# Sheet2.net
KiCad netlist of a schematic drawn in Altium Designer
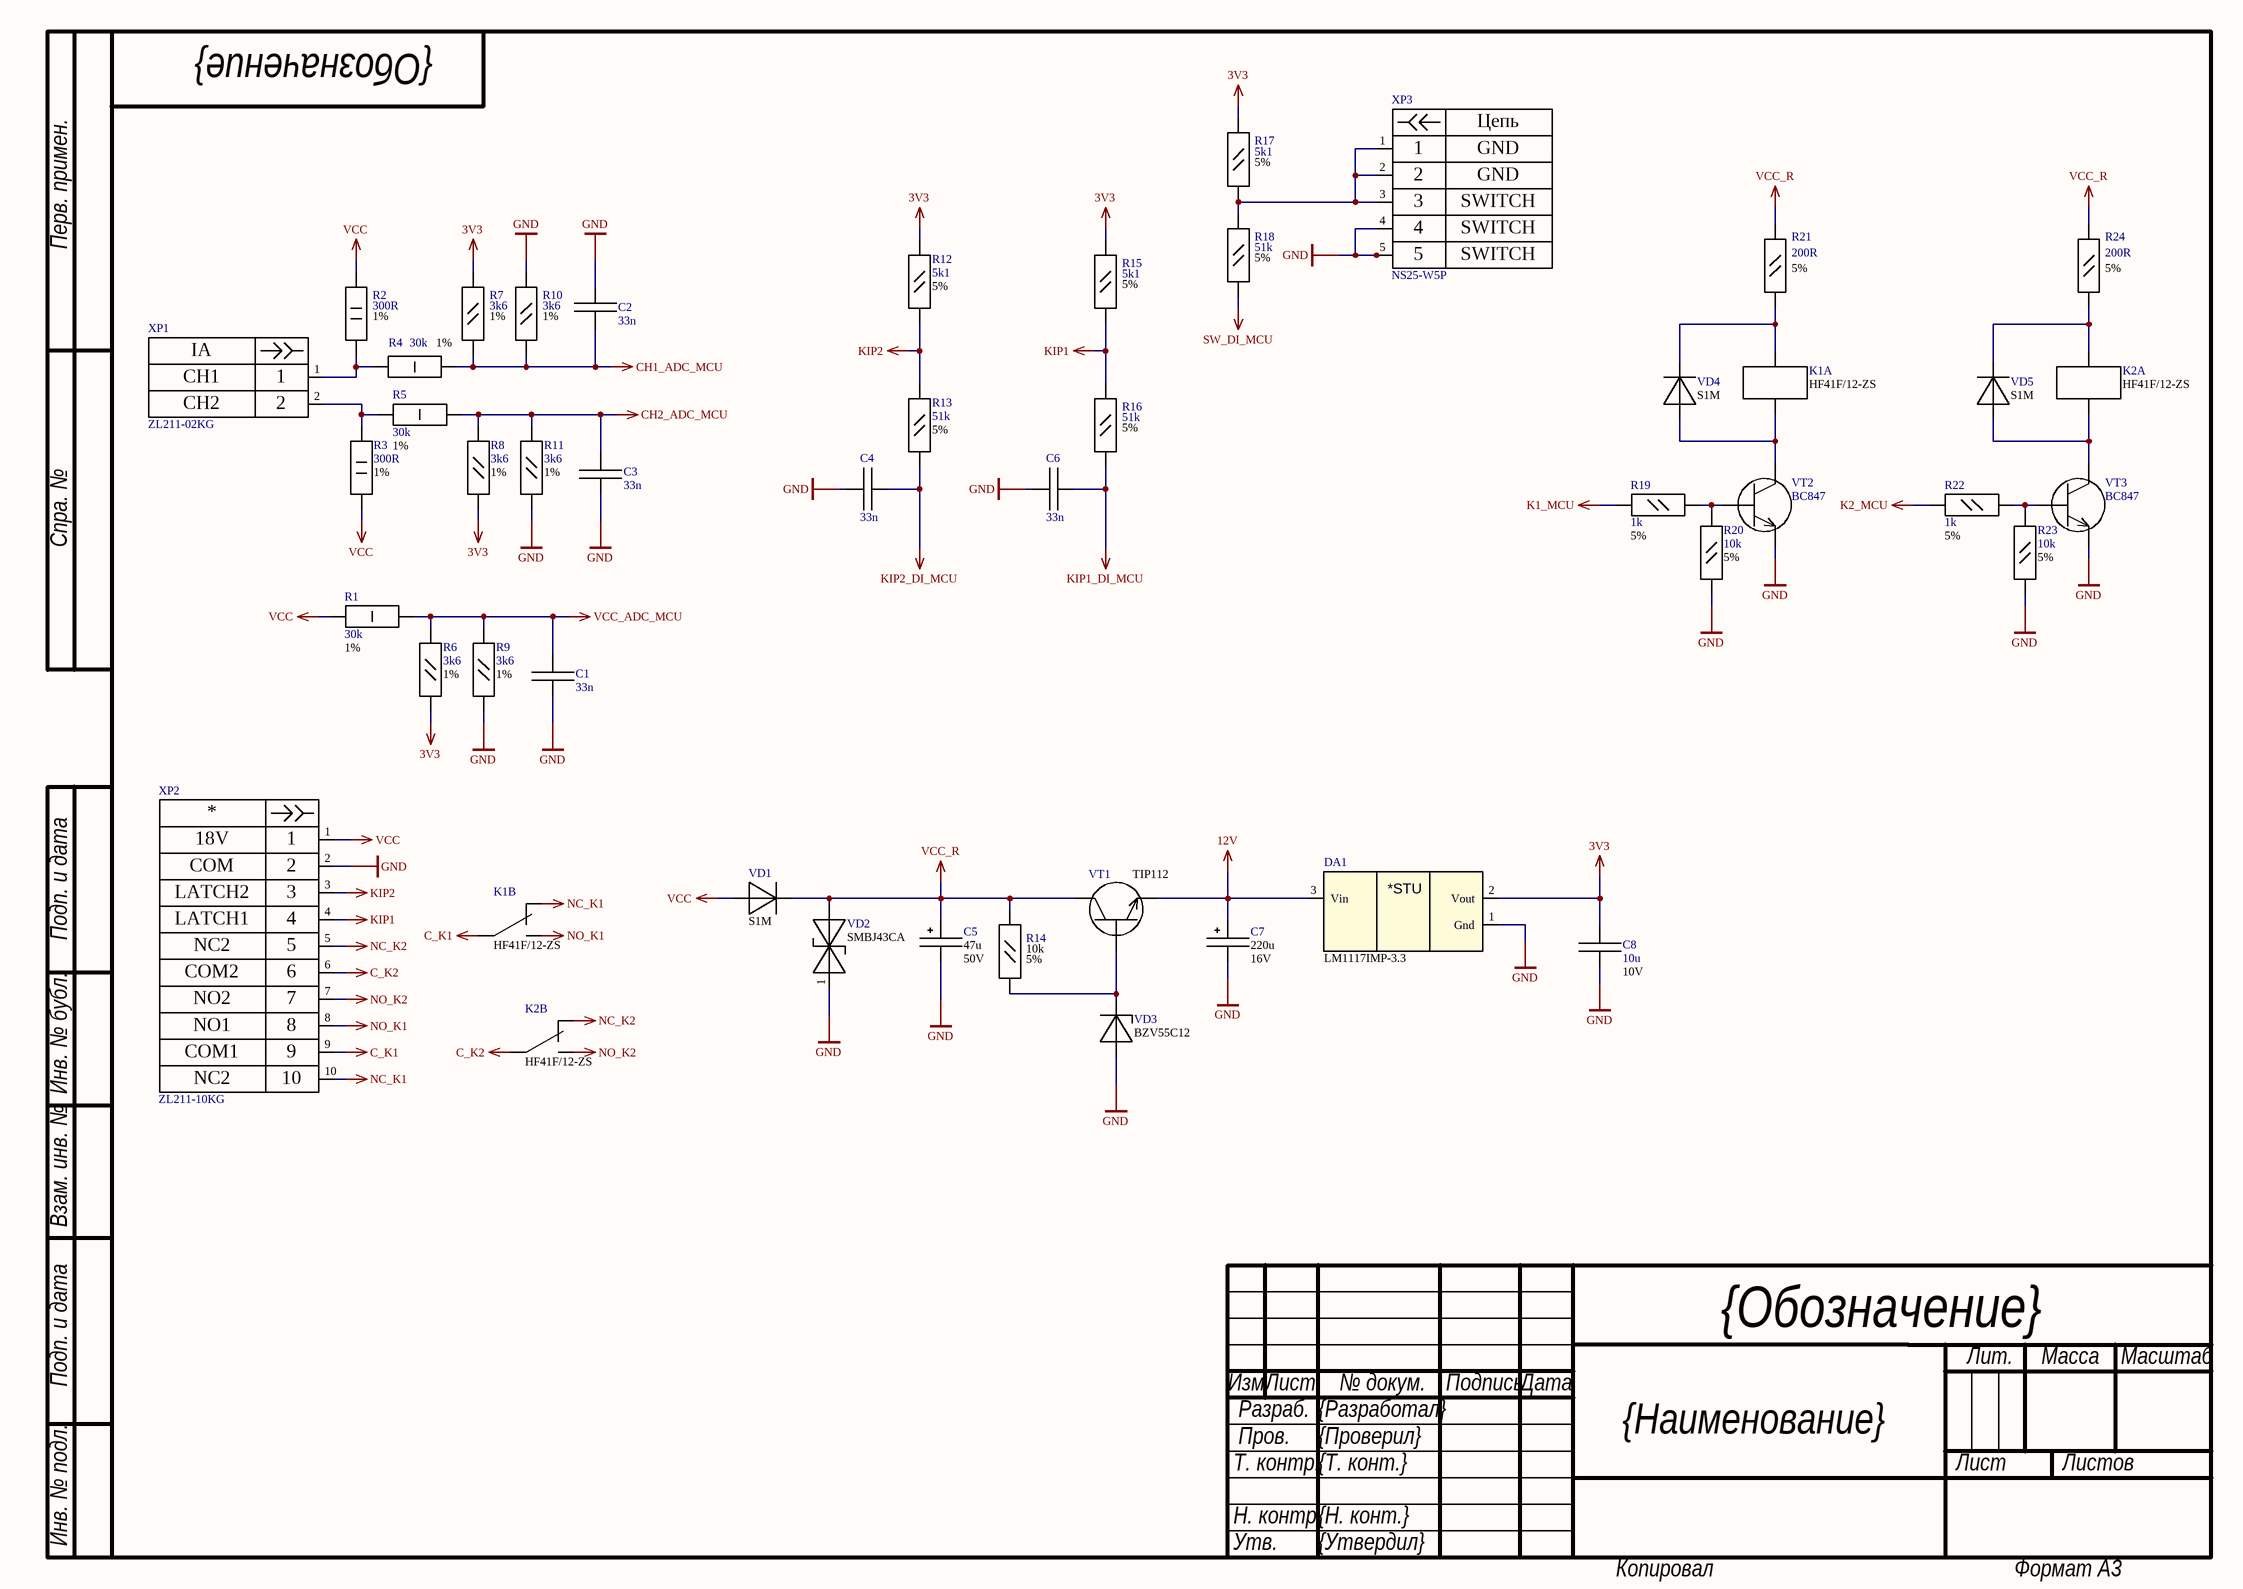
[diagram p0: Sheet2.SchDoc]

(export (version "E")
  (design (tool "Eeschema 10.0.6"))
  (components
    (comp (ref "C1") (value "33n") (footprint "Cap Ceramic 0805") (libsource (lib "Россыпь") (part "CerCap")))
    (comp (ref "C2") (value "33n") (footprint "Cap Ceramic 0805") (libsource (lib "Россыпь") (part "CerCap")))
    (comp (ref "C3") (value "33n") (footprint "Cap Ceramic 0805") (libsource (lib "Россыпь") (part "CerCap")))
    (comp (ref "C4") (value "33n") (footprint "Cap Ceramic 0805") (libsource (lib "Россыпь") (part "CerCap")))
    (comp (ref "C5")
      (value "47u")
      (footprint "Cap electro d6.3x2.54mm")
      (fields (field (name "COMMENTS") "50V"))
      (libsource (lib "Россыпь") (part "ECap"))
    )
    (comp (ref "C6") (value "33n") (footprint "Cap Ceramic 0805") (libsource (lib "Россыпь") (part "CerCap")))
    (comp (ref "C7")
      (value "220u")
      (footprint "Cap electro d6.3x2.54mm")
      (fields (field (name "COMMENTS") "16V"))
      (libsource (lib "Россыпь") (part "ECap"))
    )
    (comp (ref "C8")
      (value "10u")
      (footprint "Cap Ceramic 1206")
      (fields (field (name "COMMENTS") "10V"))
      (libsource (lib "Россыпь") (part "CerCap"))
    )
    (comp (ref "DA1")
      (value "LM1117IMP-3.3")
      (footprint "SOT-232")
      (libsource (lib "Россыпь") (part "LM1117IMP-x.x"))
    )
    (comp (ref "K1")
      (value "HF41F/12-ZS")
      (footprint "RM699V")
      (libsource (lib "Россыпь") (part "RM699V-xx11-85-xxxx"))
    )
    (comp (ref "K2")
      (value "HF41F/12-ZS")
      (footprint "RM699V")
      (libsource (lib "Россыпь") (part "RM699V-xx11-85-xxxx"))
    )
    (comp (ref "R1")
      (value "30k")
      (footprint "Resistor 2512")
      (fields (field (name "COMMENTS") "1%"))
      (libsource (lib "Россыпь") (part "Resistor 1W"))
    )
    (comp (ref "R2")
      (value "300R")
      (footprint "Resistor 2W d5.08x20.32 axial")
      (fields (field (name "COMMENTS") "1%"))
      (libsource (lib "Россыпь") (part "Resistor 2W"))
    )
    (comp (ref "R3")
      (value "300R")
      (footprint "Resistor 2W d5.08x20.32 axial")
      (fields (field (name "COMMENTS") "1%"))
      (libsource (lib "Россыпь") (part "Resistor 2W"))
    )
    (comp (ref "R4")
      (value "30k")
      (footprint "Resistor 2512")
      (fields (field (name "COMMENTS") "1%"))
      (libsource (lib "Россыпь") (part "Resistor 1W"))
    )
    (comp (ref "R5")
      (value "30k")
      (footprint "Resistor 2512")
      (fields (field (name "COMMENTS") "1%"))
      (libsource (lib "Россыпь") (part "Resistor 1W"))
    )
    (comp (ref "R6")
      (value "3k6")
      (footprint "Resistor 0805")
      (fields (field (name "COMMENTS") "1%"))
      (libsource (lib "Россыпь") (part "Resistor 0,125W"))
    )
    (comp (ref "R7")
      (value "3k6")
      (footprint "Resistor 0805")
      (fields (field (name "COMMENTS") "1%"))
      (libsource (lib "Россыпь") (part "Resistor 0,125W"))
    )
    (comp (ref "R8")
      (value "3k6")
      (footprint "Resistor 0805")
      (fields (field (name "COMMENTS") "1%"))
      (libsource (lib "Россыпь") (part "Resistor 0,125W"))
    )
    (comp (ref "R9")
      (value "3k6")
      (footprint "Resistor 0805")
      (fields (field (name "COMMENTS") "1%"))
      (libsource (lib "Россыпь") (part "Resistor 0,125W"))
    )
    (comp (ref "R10")
      (value "3k6")
      (footprint "Resistor 0805")
      (fields (field (name "COMMENTS") "1%"))
      (libsource (lib "Россыпь") (part "Resistor 0,125W"))
    )
    (comp (ref "R11")
      (value "3k6")
      (footprint "Resistor 0805")
      (fields (field (name "COMMENTS") "1%"))
      (libsource (lib "Россыпь") (part "Resistor 0,125W"))
    )
    (comp (ref "R12")
      (value "5k1")
      (footprint "Resistor 0805")
      (fields (field (name "COMMENTS") "5%"))
      (libsource (lib "Россыпь") (part "Resistor 0,125W"))
    )
    (comp (ref "R13")
      (value "51k")
      (footprint "Resistor 0805")
      (fields (field (name "COMMENTS") "5%"))
      (libsource (lib "Россыпь") (part "Resistor 0,125W"))
    )
    (comp (ref "R14")
      (value "10k")
      (footprint "Resistor 0805")
      (fields (field (name "COMMENTS") "5%"))
      (libsource (lib "Россыпь") (part "Resistor 0,125W"))
    )
    (comp (ref "R15")
      (value "5k1")
      (footprint "Resistor 0805")
      (fields (field (name "COMMENTS") "5%"))
      (libsource (lib "Россыпь") (part "Resistor 0,125W"))
    )
    (comp (ref "R16")
      (value "51k")
      (footprint "Resistor 0805")
      (fields (field (name "COMMENTS") "5%"))
      (libsource (lib "Россыпь") (part "Resistor 0,125W"))
    )
    (comp (ref "R17")
      (value "5k1")
      (footprint "Resistor 0805")
      (fields (field (name "COMMENTS") "5%"))
      (libsource (lib "Россыпь") (part "Resistor 0,125W"))
    )
    (comp (ref "R18")
      (value "51k")
      (footprint "Resistor 0805")
      (fields (field (name "COMMENTS") "5%"))
      (libsource (lib "Россыпь") (part "Resistor 0,125W"))
    )
    (comp (ref "R19")
      (value "1k")
      (footprint "Resistor 0805")
      (fields (field (name "COMMENTS") "5%"))
      (libsource (lib "Россыпь") (part "Resistor 0,125W"))
    )
    (comp (ref "R20")
      (value "10k")
      (footprint "Resistor 0805")
      (fields (field (name "COMMENTS") "5%"))
      (libsource (lib "Россыпь") (part "Resistor 0,125W"))
    )
    (comp (ref "R21")
      (value "200R")
      (footprint "Resistor 0805")
      (fields (field (name "COMMENTS") "5%"))
      (libsource (lib "Россыпь") (part "Resistor 0,125W"))
    )
    (comp (ref "R22")
      (value "1k")
      (footprint "Resistor 0805")
      (fields (field (name "COMMENTS") "5%"))
      (libsource (lib "Россыпь") (part "Resistor 0,125W"))
    )
    (comp (ref "R23")
      (value "10k")
      (footprint "Resistor 0805")
      (fields (field (name "COMMENTS") "5%"))
      (libsource (lib "Россыпь") (part "Resistor 0,125W"))
    )
    (comp (ref "R24")
      (value "200R")
      (footprint "Resistor 0805")
      (fields (field (name "COMMENTS") "5%"))
      (libsource (lib "Россыпь") (part "Resistor 0,125W"))
    )
    (comp (ref "VD1") (value "S1M") (footprint "DO-214AC SMA") (libsource (lib "Россыпь") (part "S1M")))
    (comp (ref "VD2")
      (value "SMBJ43CA")
      (footprint "DO-214AA SMB")
      (libsource (lib "Россыпь") (part "SMBJxxCA"))
    )
    (comp (ref "VD3") (value "BZV55C12") (footprint "SOD80C") (libsource (lib "Россыпь") (part "BZV55Cxx")))
    (comp (ref "VD4") (value "S1M") (footprint "DO-214AC SMA") (libsource (lib "Россыпь") (part "S1M")))
    (comp (ref "VD5") (value "S1M") (footprint "DO-214AC SMA") (libsource (lib "Россыпь") (part "S1M")))
    (comp (ref "VT1") (value "TIP112") (footprint "TO-220") (libsource (lib "Россыпь") (part "BDW93C")))
    (comp (ref "VT2") (value "BC847") (footprint "SOT-23-3") (libsource (lib "Россыпь") (part "BC847")))
    (comp (ref "VT3") (value "BC847") (footprint "SOT-23-3") (libsource (lib "Россыпь") (part "BC847")))
    (comp (ref "XP1")
      (value "ZL211-02KG")
      (footprint "Pins 1x2")
      (fields (field (name "NAME1") "CH1") (field (name "NAME") "IA") (field (name "NAME2") "CH2"))
      (libsource (lib "Россыпь") (part "Pins 1x2"))
    )
    (comp (ref "XP2")
      (value "ZL211-10KG")
      (footprint "Pins 1x10")
      (fields
        (field (name "NAME1") "18V")
        (field (name "NAME2") "COM")
        (field (name "NAME3") "LATCH2")
        (field (name "NAME") "*")
        (field (name "NAME4") "LATCH1")
        (field (name "NAME5") "NC2")
        (field (name "NAME6") "COM2")
        (field (name "NAME7") "NO2")
        (field (name "NAME8") "NO1")
        (field (name "NAME9") "COM1")
        (field (name "NAME10") "NC2")
      )
      (libsource (lib "Россыпь") (part "Pins 1x10"))
    )
    (comp (ref "XP3")
      (value "NS25-W5P")
      (footprint "WF-05")
      (fields
        (field (name "NAME1") "GND")
        (field (name "NAME") "Цепь")
        (field (name "NAME2") "GND")
        (field (name "NAME3") "SWITCH")
        (field (name "NAME4") "SWITCH")
        (field (name "NAME5") "SWITCH")
      )
      (libsource (lib "Россыпь") (part "Pins 1x5"))
    )
  )
  (nets
    (net (code "1") (name "3V3") (class "Default")
      (node (ref "C8") (pin "2") (pinfunction "2_2") (pintype "passive"))
      (node (ref "DA1") (pin "2") (pinfunction "Vout_2") (pintype "passive"))
      (node (ref "R12") (pin "1") (pinfunction "1_1") (pintype "passive"))
      (node (ref "R15") (pin "1") (pinfunction "1_1") (pintype "passive"))
      (node (ref "R17") (pin "1") (pinfunction "1_1") (pintype "passive"))
      (node (ref "R6") (pin "1") (pinfunction "1_1") (pintype "passive"))
      (node (ref "R7") (pin "1") (pinfunction "1_1") (pintype "passive"))
      (node (ref "R8") (pin "1") (pinfunction "1_1") (pintype "passive"))
    )
    (net (code "2") (name "12V") (class "Default")
      (node (ref "C7") (pin "2") (pinfunction "2_2") (pintype "passive"))
      (node (ref "DA1") (pin "3") (pinfunction "Vin_3") (pintype "passive"))
      (node (ref "VT1") (pin "3") (pinfunction "E_3") (pintype "passive"))
    )
    (net (code "3") (name "CH1_ADC_MCU") (class "Default")
      (node (ref "C2") (pin "2") (pinfunction "2_2") (pintype "passive"))
      (node (ref "R10") (pin "2") (pinfunction "2_2") (pintype "passive"))
      (node (ref "R4") (pin "2") (pinfunction "2_2") (pintype "passive"))
      (node (ref "R7") (pin "2") (pinfunction "2_2") (pintype "passive"))
    )
    (net (code "4") (name "CH2_ADC_MCU") (class "Default")
      (node (ref "C3") (pin "2") (pinfunction "2_2") (pintype "passive"))
      (node (ref "R11") (pin "2") (pinfunction "2_2") (pintype "passive"))
      (node (ref "R5") (pin "2") (pinfunction "2_2") (pintype "passive"))
      (node (ref "R8") (pin "2") (pinfunction "2_2") (pintype "passive"))
    )
    (net (code "5") (name "C_K1") (class "Default")
      (node (ref "K1") (pin "11") (pinfunction "11_11") (pintype "passive"))
      (node (ref "XP2") (pin "9") (pinfunction "9_9") (pintype "passive"))
    )
    (net (code "6") (name "C_K2") (class "Default")
      (node (ref "K2") (pin "11") (pinfunction "11_11") (pintype "passive"))
      (node (ref "XP2") (pin "6") (pinfunction "6_6") (pintype "passive"))
    )
    (net (code "7") (name "GND") (class "Default")
      (node (ref "C1") (pin "1") (pinfunction "1_1") (pintype "passive"))
      (node (ref "C2") (pin "1") (pinfunction "1_1") (pintype "passive"))
      (node (ref "C3") (pin "1") (pinfunction "1_1") (pintype "passive"))
      (node (ref "C4") (pin "2") (pinfunction "2_2") (pintype "passive"))
      (node (ref "C5") (pin "1") (pinfunction "1_1") (pintype "passive"))
      (node (ref "C6") (pin "2") (pinfunction "2_2") (pintype "passive"))
      (node (ref "C7") (pin "1") (pinfunction "1_1") (pintype "passive"))
      (node (ref "C8") (pin "1") (pinfunction "1_1") (pintype "passive"))
      (node (ref "DA1") (pin "1") (pinfunction "Gnd_1") (pintype "passive"))
      (node (ref "R10") (pin "1") (pinfunction "1_1") (pintype "passive"))
      (node (ref "R11") (pin "1") (pinfunction "1_1") (pintype "passive"))
      (node (ref "R20") (pin "2") (pinfunction "2_2") (pintype "passive"))
      (node (ref "R23") (pin "2") (pinfunction "2_2") (pintype "passive"))
      (node (ref "R9") (pin "1") (pinfunction "1_1") (pintype "passive"))
      (node (ref "VD2") (pin "1") (pinfunction "1_1") (pintype "passive"))
      (node (ref "VD3") (pin "1") (pinfunction "A_1") (pintype "passive"))
      (node (ref "VT2") (pin "2") (pinfunction "E_2") (pintype "passive"))
      (node (ref "VT3") (pin "2") (pinfunction "E_2") (pintype "passive"))
      (node (ref "XP2") (pin "2") (pinfunction "2_2") (pintype "passive"))
      (node (ref "XP3") (pin "4") (pinfunction "4_4") (pintype "passive"))
      (node (ref "XP3") (pin "5") (pinfunction "5_5") (pintype "passive"))
    )
    (net (code "8") (name "K1_MCU") (class "Default")
      (node (ref "R19") (pin "2") (pinfunction "2_2") (pintype "passive"))
    )
    (net (code "9") (name "K2_MCU") (class "Default")
      (node (ref "R22") (pin "2") (pinfunction "2_2") (pintype "passive"))
    )
    (net (code "10") (name "KIP1") (class "Default")
      (node (ref "R15") (pin "2") (pinfunction "2_2") (pintype "passive"))
      (node (ref "R16") (pin "1") (pinfunction "1_1") (pintype "passive"))
      (node (ref "XP2") (pin "4") (pinfunction "4_4") (pintype "passive"))
    )
    (net (code "11") (name "KIP1_DI_MCU") (class "Default")
      (node (ref "C6") (pin "1") (pinfunction "1_1") (pintype "passive"))
      (node (ref "R16") (pin "2") (pinfunction "2_2") (pintype "passive"))
    )
    (net (code "12") (name "KIP2") (class "Default")
      (node (ref "R12") (pin "2") (pinfunction "2_2") (pintype "passive"))
      (node (ref "R13") (pin "1") (pinfunction "1_1") (pintype "passive"))
      (node (ref "XP2") (pin "3") (pinfunction "3_3") (pintype "passive"))
    )
    (net (code "13") (name "KIP2_DI_MCU") (class "Default")
      (node (ref "C4") (pin "1") (pinfunction "1_1") (pintype "passive"))
      (node (ref "R13") (pin "2") (pinfunction "2_2") (pintype "passive"))
    )
    (net (code "14") (name "NC_K1") (class "Default")
      (node (ref "K1") (pin "12") (pinfunction "12_12") (pintype "passive"))
      (node (ref "XP2") (pin "10") (pinfunction "10_10") (pintype "passive"))
    )
    (net (code "15") (name "NC_K2") (class "Default")
      (node (ref "K2") (pin "12") (pinfunction "12_12") (pintype "passive"))
      (node (ref "XP2") (pin "5") (pinfunction "5_5") (pintype "passive"))
    )
    (net (code "16") (name "NO_K1") (class "Default")
      (node (ref "K1") (pin "14") (pinfunction "14_14") (pintype "passive"))
      (node (ref "XP2") (pin "8") (pinfunction "8_8") (pintype "passive"))
    )
    (net (code "17") (name "NO_K2") (class "Default")
      (node (ref "K2") (pin "14") (pinfunction "14_14") (pintype "passive"))
      (node (ref "XP2") (pin "7") (pinfunction "7_7") (pintype "passive"))
    )
    (net (code "18") (name "Net-(R2-Pad1)") (class "Default")
      (node (ref "R2") (pin "1") (pinfunction "1_1") (pintype "passive"))
      (node (ref "R4") (pin "1") (pinfunction "1_1") (pintype "passive"))
      (node (ref "XP1") (pin "1") (pinfunction "1_1") (pintype "passive"))
    )
    (net (code "19") (name "Net-(R3-Pad1)") (class "Default")
      (node (ref "R3") (pin "1") (pinfunction "1_1") (pintype "passive"))
      (node (ref "R5") (pin "1") (pinfunction "1_1") (pintype "passive"))
      (node (ref "XP1") (pin "2") (pinfunction "2_2") (pintype "passive"))
    )
    (net (code "20") (name "Net-(R17-Pad2)") (class "Default")
      (node (ref "R17") (pin "2") (pinfunction "2_2") (pintype "passive"))
      (node (ref "R18") (pin "1") (pinfunction "1_1") (pintype "passive"))
      (node (ref "XP3") (pin "1") (pinfunction "1_1") (pintype "passive"))
      (node (ref "XP3") (pin "2") (pinfunction "2_2") (pintype "passive"))
      (node (ref "XP3") (pin "3") (pinfunction "3_3") (pintype "passive"))
    )
    (net (code "21") (name "Net-(VD3-K)") (class "Default")
      (node (ref "R14") (pin "2") (pinfunction "2_2") (pintype "passive"))
      (node (ref "VD3") (pin "2") (pinfunction "K_2") (pintype "passive"))
      (node (ref "VT1") (pin "1") (pinfunction "B_1") (pintype "passive"))
    )
    (net (code "22") (name "Net-(VD4-A)") (class "Default")
      (node (ref "K1") (pin "2") (pinfunction "2_2") (pintype "passive"))
      (node (ref "VD4") (pin "1") (pinfunction "A_1") (pintype "passive"))
      (node (ref "VT2") (pin "3") (pinfunction "K_3") (pintype "passive"))
    )
    (net (code "23") (name "Net-(VD4-K)") (class "Default")
      (node (ref "K1") (pin "1") (pinfunction "1_1") (pintype "passive"))
      (node (ref "R21") (pin "1") (pinfunction "1_1") (pintype "passive"))
      (node (ref "VD4") (pin "2") (pinfunction "K_2") (pintype "passive"))
    )
    (net (code "24") (name "Net-(VD5-A)") (class "Default")
      (node (ref "K2") (pin "2") (pinfunction "2_2") (pintype "passive"))
      (node (ref "VD5") (pin "1") (pinfunction "A_1") (pintype "passive"))
      (node (ref "VT3") (pin "3") (pinfunction "K_3") (pintype "passive"))
    )
    (net (code "25") (name "Net-(VD5-K)") (class "Default")
      (node (ref "K2") (pin "1") (pinfunction "1_1") (pintype "passive"))
      (node (ref "R24") (pin "1") (pinfunction "1_1") (pintype "passive"))
      (node (ref "VD5") (pin "2") (pinfunction "K_2") (pintype "passive"))
    )
    (net (code "26") (name "Net-(VT2-B)") (class "Default")
      (node (ref "R19") (pin "1") (pinfunction "1_1") (pintype "passive"))
      (node (ref "R20") (pin "1") (pinfunction "1_1") (pintype "passive"))
      (node (ref "VT2") (pin "1") (pinfunction "B_1") (pintype "passive"))
    )
    (net (code "27") (name "Net-(VT3-B)") (class "Default")
      (node (ref "R22") (pin "1") (pinfunction "1_1") (pintype "passive"))
      (node (ref "R23") (pin "1") (pinfunction "1_1") (pintype "passive"))
      (node (ref "VT3") (pin "1") (pinfunction "B_1") (pintype "passive"))
    )
    (net (code "28") (name "SW_DI_MCU") (class "Default")
      (node (ref "R18") (pin "2") (pinfunction "2_2") (pintype "passive"))
    )
    (net (code "29") (name "VCC") (class "Default")
      (node (ref "R1") (pin "1") (pinfunction "1_1") (pintype "passive"))
      (node (ref "R2") (pin "2") (pinfunction "2_2") (pintype "passive"))
      (node (ref "R3") (pin "2") (pinfunction "2_2") (pintype "passive"))
      (node (ref "VD1") (pin "1") (pinfunction "A_1") (pintype "passive"))
      (node (ref "XP2") (pin "1") (pinfunction "1_1") (pintype "passive"))
    )
    (net (code "30") (name "VCC_ADC_MCU") (class "Default")
      (node (ref "C1") (pin "2") (pinfunction "2_2") (pintype "passive"))
      (node (ref "R1") (pin "2") (pinfunction "2_2") (pintype "passive"))
      (node (ref "R6") (pin "2") (pinfunction "2_2") (pintype "passive"))
      (node (ref "R9") (pin "2") (pinfunction "2_2") (pintype "passive"))
    )
    (net (code "31") (name "VCC_R") (class "Default")
      (node (ref "C5") (pin "2") (pinfunction "2_2") (pintype "passive"))
      (node (ref "R14") (pin "1") (pinfunction "1_1") (pintype "passive"))
      (node (ref "R21") (pin "2") (pinfunction "2_2") (pintype "passive"))
      (node (ref "R24") (pin "2") (pinfunction "2_2") (pintype "passive"))
      (node (ref "VD1") (pin "2") (pinfunction "K_2") (pintype "passive"))
      (node (ref "VD2") (pin "2") (pinfunction "2_2") (pintype "passive"))
      (node (ref "VT1") (pin "2") (pinfunction "K_2") (pintype "passive"))
    )
  )
)
